# 4_Darlington_Pair_Amplifier.net
KiCad netlist of a schematic drawn in Altium Designer
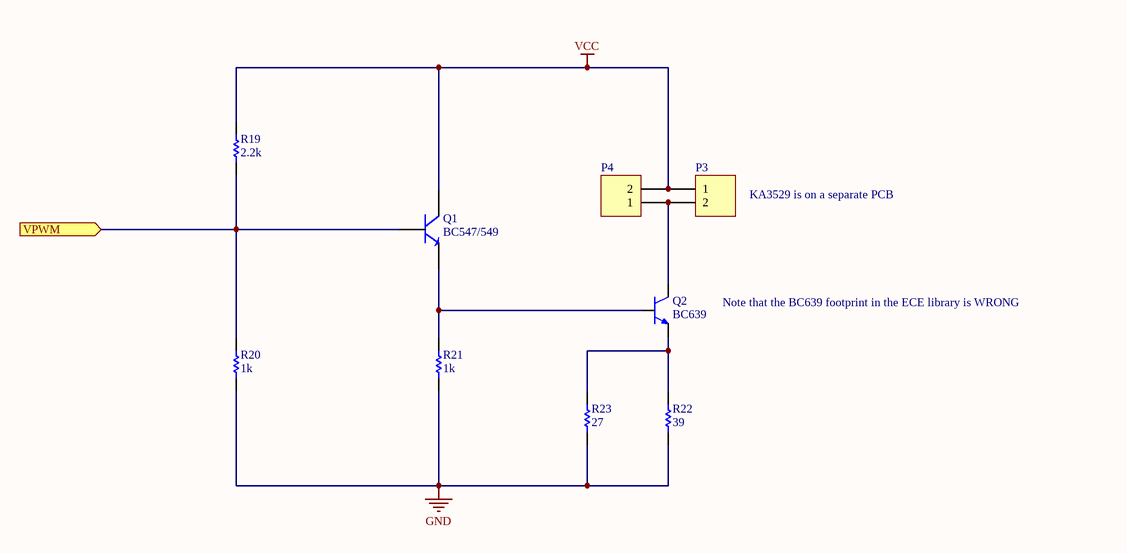
[diagram p0: 4_Darlington Pair Amplifier.SchDoc]

(export (version "E")
  (design (tool "Eeschema 10.0.6"))
  (components
    (comp (ref "P3")
      (value "Header 2")
      (footprint "ece-HDR1X2")
      (description "Header, 2-Pin")
      (fields (field (name "PUBLISHER") "Altium Limited"))
      (libsource (lib "") (part "Header 2_1"))
    )
    (comp (ref "P4")
      (value "Header 2")
      (footprint "ece-HDR1X2")
      (description "Header, 2-Pin")
      (fields (field (name "PUBLISHER") "Altium Limited"))
      (libsource (lib "ece components") (part "Header 2"))
    )
    (comp (ref "Q1")
      (value "BC547/549")
      (footprint "ece-TO-92Z")
      (description "NPN Transistor")
      (libsource (lib "ece components") (part "BC547/549"))
    )
    (comp (ref "Q2")
      (value "BC639")
      (footprint "TO92")
      (description "BC639 with correct footprint")
      (libsource (lib "EE310_example") (part "BC639"))
    )
    (comp (ref "R19")
      (value "2.2k")
      (footprint "ece-AXIAL0.4")
      (description "Resistor")
      (fields (field (name "PUBLISHER") "Altium Limited"))
      (libsource (lib "ece components") (part "Res1"))
    )
    (comp (ref "R20")
      (value "1k")
      (footprint "ece-AXIAL0.4")
      (description "Resistor")
      (fields (field (name "PUBLISHER") "Altium Limited"))
      (libsource (lib "ece components") (part "Res1"))
    )
    (comp (ref "R21")
      (value "1k")
      (footprint "ece-AXIAL0.4")
      (description "Resistor")
      (fields (field (name "PUBLISHER") "Altium Limited"))
      (libsource (lib "ece components") (part "Res1"))
    )
    (comp (ref "R22")
      (value "39")
      (footprint "ece-AXIAL0.4")
      (description "Resistor")
      (fields (field (name "PUBLISHER") "Altium Limited"))
      (libsource (lib "ece components") (part "Res1"))
    )
    (comp (ref "R23")
      (value "27")
      (footprint "ece-AXIAL0.4")
      (description "Resistor")
      (fields (field (name "PUBLISHER") "Altium Limited"))
      (libsource (lib "ece components") (part "Res1"))
    )
  )
  (nets
    (net (code "1") (name "/VPWM") (class "Default")
      (node (ref "Q1") (pin "2") (pinfunction "B_2") (pintype "passive"))
      (node (ref "R19") (pin "2") (pinfunction "2_2") (pintype "passive"))
      (node (ref "R20") (pin "1") (pinfunction "1_1") (pintype "passive"))
    )
    (net (code "2") (name "GND") (class "Default")
      (node (ref "R20") (pin "2") (pinfunction "2_2") (pintype "passive"))
      (node (ref "R21") (pin "2") (pinfunction "2_2") (pintype "passive"))
      (node (ref "R22") (pin "2") (pinfunction "2_2") (pintype "passive"))
      (node (ref "R23") (pin "2") (pinfunction "2_2") (pintype "passive"))
    )
    (net (code "3") (name "Net-(P3-Pad2)") (class "Default")
      (node (ref "P3") (pin "2") (pinfunction "2_2") (pintype "passive"))
      (node (ref "P4") (pin "1") (pinfunction "1_1") (pintype "passive"))
      (node (ref "Q2") (pin "2") (pinfunction "2_2") (pintype "passive"))
    )
    (net (code "4") (name "Net-(Q1-E)") (class "Default")
      (node (ref "Q1") (pin "3") (pinfunction "E_3") (pintype "passive"))
      (node (ref "Q2") (pin "3") (pinfunction "3_3") (pintype "passive"))
      (node (ref "R21") (pin "1") (pinfunction "1_1") (pintype "passive"))
    )
    (net (code "5") (name "Net-(Q2-Pad1)") (class "Default")
      (node (ref "Q2") (pin "1") (pinfunction "1_1") (pintype "passive"))
      (node (ref "R22") (pin "1") (pinfunction "1_1") (pintype "passive"))
      (node (ref "R23") (pin "1") (pinfunction "1_1") (pintype "passive"))
    )
    (net (code "6") (name "VCC") (class "Default")
      (node (ref "P3") (pin "1") (pinfunction "1_1") (pintype "passive"))
      (node (ref "P4") (pin "2") (pinfunction "2_2") (pintype "passive"))
      (node (ref "Q1") (pin "1") (pinfunction "C_1") (pintype "passive"))
      (node (ref "R19") (pin "1") (pinfunction "1_1") (pintype "passive"))
    )
  )
)
